# 03_ICs.net
KiCad netlist of a schematic drawn in Altium Designer
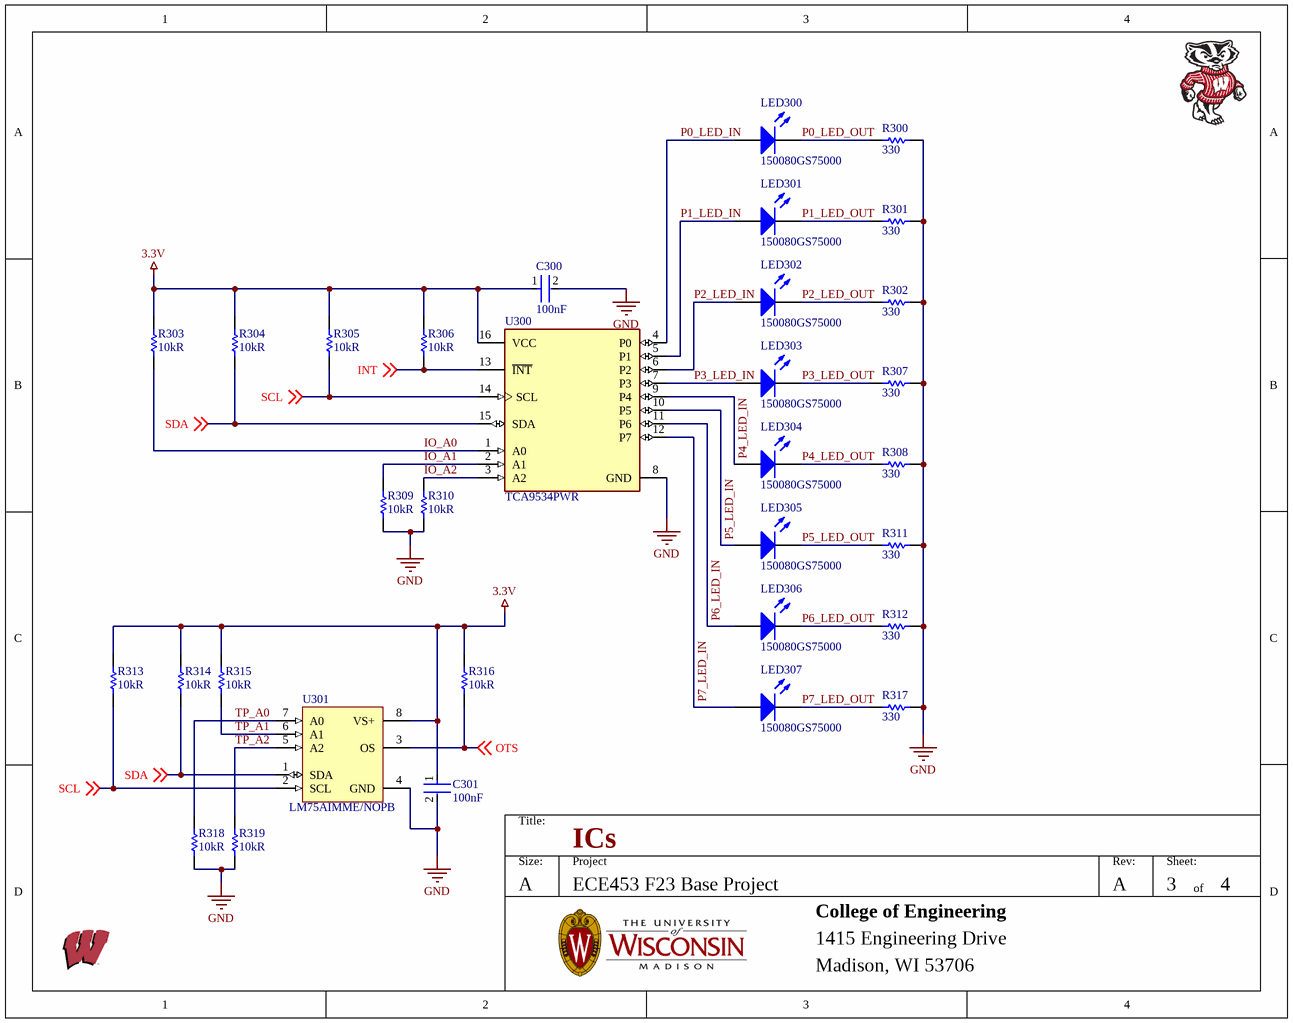
[diagram p0: 03_ICs.SchDoc]

(export (version "E")
  (design (tool "Eeschema 10.0.6"))
  (components
    (comp (ref "C300")
      (value "100nF")
      (footprint "FP-C0805C-DN-MFG")
      (description "CAP CER 0.1UF 50V X7R 0805")
      (fields
        (field (name "MANUFACTURER") "KEMET")
        (field (name "MANUFACTURER PART NUMBER") "C0805C104K5RACTU")
      )
      (libsource (lib "ECE453") (part "CMP-2007-00279-2"))
    )
    (comp (ref "C301")
      (value "100nF")
      (footprint "FP-C0805C-DN-MFG")
      (description "CAP CER 0.1UF 50V X7R 0805")
      (fields
        (field (name "MANUFACTURER") "KEMET")
        (field (name "MANUFACTURER PART NUMBER") "C0805C104K5RACTU")
      )
      (libsource (lib "ECE453") (part "CMP-2007-00279-2"))
    )
    (comp (ref "LED300")
      (value "150080GS75000")
      (footprint "0805_A")
      (description "SMD mono-color Chip LED, WL-SMCW, Green")
      (fields (field (name "MANUFACTURER") "Wuerth Elektronik"))
      (libsource (lib "ECE453") (part "CMP-1426-00007-1"))
    )
    (comp (ref "LED301")
      (value "150080GS75000")
      (footprint "0805_A")
      (description "SMD mono-color Chip LED, WL-SMCW, Green")
      (fields (field (name "MANUFACTURER") "Wuerth Elektronik"))
      (libsource (lib "ECE453") (part "CMP-1426-00007-1"))
    )
    (comp (ref "LED302")
      (value "150080GS75000")
      (footprint "0805_A")
      (description "SMD mono-color Chip LED, WL-SMCW, Green")
      (fields (field (name "MANUFACTURER") "Wuerth Elektronik"))
      (libsource (lib "ECE453") (part "CMP-1426-00007-1"))
    )
    (comp (ref "LED303")
      (value "150080GS75000")
      (footprint "0805_A")
      (description "SMD mono-color Chip LED, WL-SMCW, Green")
      (fields (field (name "MANUFACTURER") "Wuerth Elektronik"))
      (libsource (lib "ECE453") (part "CMP-1426-00007-1"))
    )
    (comp (ref "LED304")
      (value "150080GS75000")
      (footprint "0805_A")
      (description "SMD mono-color Chip LED, WL-SMCW, Green")
      (fields (field (name "MANUFACTURER") "Wuerth Elektronik"))
      (libsource (lib "ECE453") (part "CMP-1426-00007-1"))
    )
    (comp (ref "LED305")
      (value "150080GS75000")
      (footprint "0805_A")
      (description "SMD mono-color Chip LED, WL-SMCW, Green")
      (fields (field (name "MANUFACTURER") "Wuerth Elektronik"))
      (libsource (lib "ECE453") (part "CMP-1426-00007-1"))
    )
    (comp (ref "LED306")
      (value "150080GS75000")
      (footprint "0805_A")
      (description "SMD mono-color Chip LED, WL-SMCW, Green")
      (fields (field (name "MANUFACTURER") "Wuerth Elektronik"))
      (libsource (lib "ECE453") (part "CMP-1426-00007-1"))
    )
    (comp (ref "LED307")
      (value "150080GS75000")
      (footprint "0805_A")
      (description "SMD mono-color Chip LED, WL-SMCW, Green")
      (fields (field (name "MANUFACTURER") "Wuerth Elektronik"))
      (libsource (lib "ECE453") (part "CMP-1426-00007-1"))
    )
    (comp (ref "R300")
      (value "RC0805FR-07330RL")
      (footprint "RESC2013X60X35LL10T20")
      (description "Chip Resistor, 330 Ohm, +/- 1%, 125 mW, -55 to 155 degC, 0805 (2012 Metric), RoHS, Tape and Reel")
      (fields
        (field (name "MANUFACTURER") "Yageo")
        (field (name "TOLERANCE") "1%")
        (field (name "RESISTANCE") "330")
      )
      (libsource (lib "ECE453") (part "CMP-2000-06960-1"))
    )
    (comp (ref "R301")
      (value "RC0805FR-07330RL")
      (footprint "RESC2013X60X35LL10T20")
      (description "Chip Resistor, 330 Ohm, +/- 1%, 125 mW, -55 to 155 degC, 0805 (2012 Metric), RoHS, Tape and Reel")
      (fields
        (field (name "MANUFACTURER") "Yageo")
        (field (name "TOLERANCE") "1%")
        (field (name "RESISTANCE") "330")
      )
      (libsource (lib "ECE453") (part "CMP-2000-06960-1"))
    )
    (comp (ref "R302")
      (value "RC0805FR-07330RL")
      (footprint "RESC2013X60X35LL10T20")
      (description "Chip Resistor, 330 Ohm, +/- 1%, 125 mW, -55 to 155 degC, 0805 (2012 Metric), RoHS, Tape and Reel")
      (fields
        (field (name "MANUFACTURER") "Yageo")
        (field (name "TOLERANCE") "1%")
        (field (name "RESISTANCE") "330")
      )
      (libsource (lib "ECE453") (part "CMP-2000-06960-1"))
    )
    (comp (ref "R303")
      (value "RC0805FR-0710KL")
      (footprint "RESC2013X60X35NL10T20")
      (description "Chip Resistor, 10 KOhm, +/- 1%, 0.125 W, -55 to 155 degC, 0805 (2012 Metric), RoHS, Tape and Reel")
      (fields
        (field (name "MANUFACTURER") "Yageo")
        (field (name "RESISTANCE") "10kR")
        (field (name "TOLERANCE") "1%")
      )
      (libsource (lib "ECE453") (part "CMP-1659-00013-4"))
    )
    (comp (ref "R304")
      (value "RC0805FR-0710KL")
      (footprint "RESC2013X60X35NL10T20")
      (description "Chip Resistor, 10 KOhm, +/- 1%, 0.125 W, -55 to 155 degC, 0805 (2012 Metric), RoHS, Tape and Reel")
      (fields
        (field (name "MANUFACTURER") "Yageo")
        (field (name "RESISTANCE") "10kR")
        (field (name "TOLERANCE") "1%")
      )
      (libsource (lib "ECE453") (part "CMP-1659-00013-4"))
    )
    (comp (ref "R305")
      (value "RC0805FR-0710KL")
      (footprint "RESC2013X60X35NL10T20")
      (description "Chip Resistor, 10 KOhm, +/- 1%, 0.125 W, -55 to 155 degC, 0805 (2012 Metric), RoHS, Tape and Reel")
      (fields
        (field (name "MANUFACTURER") "Yageo")
        (field (name "RESISTANCE") "10kR")
        (field (name "TOLERANCE") "1%")
      )
      (libsource (lib "ECE453") (part "CMP-1659-00013-4"))
    )
    (comp (ref "R306")
      (value "RC0805FR-0710KL")
      (footprint "RESC2013X60X35NL10T20")
      (description "Chip Resistor, 10 KOhm, +/- 1%, 0.125 W, -55 to 155 degC, 0805 (2012 Metric), RoHS, Tape and Reel")
      (fields
        (field (name "MANUFACTURER") "Yageo")
        (field (name "RESISTANCE") "10kR")
        (field (name "TOLERANCE") "1%")
      )
      (libsource (lib "ECE453") (part "CMP-1659-00013-4"))
    )
    (comp (ref "R307")
      (value "RC0805FR-07330RL")
      (footprint "RESC2013X60X35LL10T20")
      (description "Chip Resistor, 330 Ohm, +/- 1%, 125 mW, -55 to 155 degC, 0805 (2012 Metric), RoHS, Tape and Reel")
      (fields
        (field (name "MANUFACTURER") "Yageo")
        (field (name "TOLERANCE") "1%")
        (field (name "RESISTANCE") "330")
      )
      (libsource (lib "ECE453") (part "CMP-2000-06960-1"))
    )
    (comp (ref "R308")
      (value "RC0805FR-07330RL")
      (footprint "RESC2013X60X35LL10T20")
      (description "Chip Resistor, 330 Ohm, +/- 1%, 125 mW, -55 to 155 degC, 0805 (2012 Metric), RoHS, Tape and Reel")
      (fields
        (field (name "MANUFACTURER") "Yageo")
        (field (name "TOLERANCE") "1%")
        (field (name "RESISTANCE") "330")
      )
      (libsource (lib "ECE453") (part "CMP-2000-06960-1"))
    )
    (comp (ref "R309")
      (value "RC0805FR-0710KL")
      (footprint "RESC2013X60X35NL10T20")
      (description "Chip Resistor, 10 KOhm, +/- 1%, 0.125 W, -55 to 155 degC, 0805 (2012 Metric), RoHS, Tape and Reel")
      (fields
        (field (name "MANUFACTURER") "Yageo")
        (field (name "RESISTANCE") "10kR")
        (field (name "TOLERANCE") "1%")
      )
      (libsource (lib "ECE453") (part "CMP-1659-00013-4"))
    )
    (comp (ref "R310")
      (value "RC0805FR-0710KL")
      (footprint "RESC2013X60X35NL10T20")
      (description "Chip Resistor, 10 KOhm, +/- 1%, 0.125 W, -55 to 155 degC, 0805 (2012 Metric), RoHS, Tape and Reel")
      (fields
        (field (name "MANUFACTURER") "Yageo")
        (field (name "RESISTANCE") "10kR")
        (field (name "TOLERANCE") "1%")
      )
      (libsource (lib "ECE453") (part "CMP-1659-00013-4"))
    )
    (comp (ref "R311")
      (value "RC0805FR-07330RL")
      (footprint "RESC2013X60X35LL10T20")
      (description "Chip Resistor, 330 Ohm, +/- 1%, 125 mW, -55 to 155 degC, 0805 (2012 Metric), RoHS, Tape and Reel")
      (fields
        (field (name "MANUFACTURER") "Yageo")
        (field (name "TOLERANCE") "1%")
        (field (name "RESISTANCE") "330")
      )
      (libsource (lib "ECE453") (part "CMP-2000-06960-1"))
    )
    (comp (ref "R312")
      (value "RC0805FR-07330RL")
      (footprint "RESC2013X60X35LL10T20")
      (description "Chip Resistor, 330 Ohm, +/- 1%, 125 mW, -55 to 155 degC, 0805 (2012 Metric), RoHS, Tape and Reel")
      (fields
        (field (name "MANUFACTURER") "Yageo")
        (field (name "TOLERANCE") "1%")
        (field (name "RESISTANCE") "330")
      )
      (libsource (lib "ECE453") (part "CMP-2000-06960-1"))
    )
    (comp (ref "R313")
      (value "RC0805FR-0710KL")
      (footprint "RESC2013X60X35NL10T20")
      (description "Chip Resistor, 10 KOhm, +/- 1%, 0.125 W, -55 to 155 degC, 0805 (2012 Metric), RoHS, Tape and Reel")
      (fields
        (field (name "MANUFACTURER") "Yageo")
        (field (name "RESISTANCE") "10kR")
        (field (name "TOLERANCE") "1%")
      )
      (libsource (lib "ECE453") (part "CMP-1659-00013-4"))
    )
    (comp (ref "R314")
      (value "RC0805FR-0710KL")
      (footprint "RESC2013X60X35NL10T20")
      (description "Chip Resistor, 10 KOhm, +/- 1%, 0.125 W, -55 to 155 degC, 0805 (2012 Metric), RoHS, Tape and Reel")
      (fields
        (field (name "MANUFACTURER") "Yageo")
        (field (name "RESISTANCE") "10kR")
        (field (name "TOLERANCE") "1%")
      )
      (libsource (lib "ECE453") (part "CMP-1659-00013-4"))
    )
    (comp (ref "R315")
      (value "RC0805FR-0710KL")
      (footprint "RESC2013X60X35NL10T20")
      (description "Chip Resistor, 10 KOhm, +/- 1%, 0.125 W, -55 to 155 degC, 0805 (2012 Metric), RoHS, Tape and Reel")
      (fields
        (field (name "MANUFACTURER") "Yageo")
        (field (name "RESISTANCE") "10kR")
        (field (name "TOLERANCE") "1%")
      )
      (libsource (lib "ECE453") (part "CMP-1659-00013-4"))
    )
    (comp (ref "R316")
      (value "RC0805FR-0710KL")
      (footprint "RESC2013X60X35NL10T20")
      (description "Chip Resistor, 10 KOhm, +/- 1%, 0.125 W, -55 to 155 degC, 0805 (2012 Metric), RoHS, Tape and Reel")
      (fields
        (field (name "MANUFACTURER") "Yageo")
        (field (name "RESISTANCE") "10kR")
        (field (name "TOLERANCE") "1%")
      )
      (libsource (lib "ECE453") (part "CMP-1659-00013-4"))
    )
    (comp (ref "R317")
      (value "RC0805FR-07330RL")
      (footprint "RESC2013X60X35LL10T20")
      (description "Chip Resistor, 330 Ohm, +/- 1%, 125 mW, -55 to 155 degC, 0805 (2012 Metric), RoHS, Tape and Reel")
      (fields
        (field (name "MANUFACTURER") "Yageo")
        (field (name "TOLERANCE") "1%")
        (field (name "RESISTANCE") "330")
      )
      (libsource (lib "ECE453") (part "CMP-2000-06960-1"))
    )
    (comp (ref "R318")
      (value "RC0805FR-0710KL")
      (footprint "RESC2013X60X35NL10T20")
      (description "Chip Resistor, 10 KOhm, +/- 1%, 0.125 W, -55 to 155 degC, 0805 (2012 Metric), RoHS, Tape and Reel")
      (fields
        (field (name "MANUFACTURER") "Yageo")
        (field (name "RESISTANCE") "10kR")
        (field (name "TOLERANCE") "1%")
      )
      (libsource (lib "ECE453") (part "CMP-1659-00013-4"))
    )
    (comp (ref "R319")
      (value "RC0805FR-0710KL")
      (footprint "RESC2013X60X35NL10T20")
      (description "Chip Resistor, 10 KOhm, +/- 1%, 0.125 W, -55 to 155 degC, 0805 (2012 Metric), RoHS, Tape and Reel")
      (fields
        (field (name "MANUFACTURER") "Yageo")
        (field (name "RESISTANCE") "10kR")
        (field (name "TOLERANCE") "1%")
      )
      (libsource (lib "ECE453") (part "CMP-1659-00013-4"))
    )
    (comp (ref "U300")
      (value "TCA9534PWR")
      (footprint "FP-PW0016A-IPC_C")
      (description "IC I/O EXPANDER I2C 8B 16TSSOP")
      (libsource (lib "ECE453") (part "CMP-04886-000003-2"))
    )
    (comp (ref "U301")
      (value "LM75AIMME/NOPB")
      (footprint "DGK0008A_L")
      (description "Digital Temperature Sensor and Thermal Watchdog with Two-Wire Interface, 8-pin Mini SOIC, Pb-Free")
      (fields (field (name "MANUFACTURER") "Texas Instruments"))
      (libsource (lib "Altium Content Vault") (part "SEN-TEMP-LM75-8"))
    )
  )
  (nets
    (net (code "1") (name "/IO_A0") (class "Default")
      (node (ref "R303") (pin "1") (pinfunction "1_1") (pintype "passive"))
      (node (ref "U300") (pin "1") (pinfunction "A0_1") (pintype "input"))
    )
    (net (code "2") (name "/IO_A1") (class "Default")
      (node (ref "R309") (pin "2") (pinfunction "2_2") (pintype "passive"))
      (node (ref "U300") (pin "2") (pinfunction "A1_2") (pintype "input"))
    )
    (net (code "3") (name "/IO_A2") (class "Default")
      (node (ref "R310") (pin "2") (pinfunction "2_2") (pintype "passive"))
      (node (ref "U300") (pin "3") (pinfunction "A2_3") (pintype "input"))
    )
    (net (code "4") (name "/P0_LED_IN") (class "Default")
      (node (ref "LED300") (pin "2") (pinfunction "A_2") (pintype "passive"))
      (node (ref "U300") (pin "4") (pinfunction "P0_4") (pintype "bidirectional"))
    )
    (net (code "5") (name "/P0_LED_OUT") (class "Default")
      (node (ref "LED300") (pin "1") (pinfunction "K_1") (pintype "passive"))
      (node (ref "R300") (pin "1") (pinfunction "1_1") (pintype "passive"))
    )
    (net (code "6") (name "/P1_LED_IN") (class "Default")
      (node (ref "LED301") (pin "2") (pinfunction "A_2") (pintype "passive"))
      (node (ref "U300") (pin "5") (pinfunction "P1_5") (pintype "bidirectional"))
    )
    (net (code "7") (name "/P1_LED_OUT") (class "Default")
      (node (ref "LED301") (pin "1") (pinfunction "K_1") (pintype "passive"))
      (node (ref "R301") (pin "1") (pinfunction "1_1") (pintype "passive"))
    )
    (net (code "8") (name "/P2_LED_IN") (class "Default")
      (node (ref "LED302") (pin "2") (pinfunction "A_2") (pintype "passive"))
      (node (ref "U300") (pin "6") (pinfunction "P2_6") (pintype "bidirectional"))
    )
    (net (code "9") (name "/P2_LED_OUT") (class "Default")
      (node (ref "LED302") (pin "1") (pinfunction "K_1") (pintype "passive"))
      (node (ref "R302") (pin "1") (pinfunction "1_1") (pintype "passive"))
    )
    (net (code "10") (name "/P3_LED_IN") (class "Default")
      (node (ref "LED303") (pin "2") (pinfunction "A_2") (pintype "passive"))
      (node (ref "U300") (pin "7") (pinfunction "P3_7") (pintype "bidirectional"))
    )
    (net (code "11") (name "/P3_LED_OUT") (class "Default")
      (node (ref "LED303") (pin "1") (pinfunction "K_1") (pintype "passive"))
      (node (ref "R307") (pin "1") (pinfunction "1_1") (pintype "passive"))
    )
    (net (code "12") (name "/P4_LED_IN") (class "Default")
      (node (ref "LED304") (pin "2") (pinfunction "A_2") (pintype "passive"))
      (node (ref "U300") (pin "9") (pinfunction "P4_9") (pintype "bidirectional"))
    )
    (net (code "13") (name "/P4_LED_OUT") (class "Default")
      (node (ref "LED304") (pin "1") (pinfunction "K_1") (pintype "passive"))
      (node (ref "R308") (pin "1") (pinfunction "1_1") (pintype "passive"))
    )
    (net (code "14") (name "/P5_LED_IN") (class "Default")
      (node (ref "LED305") (pin "2") (pinfunction "A_2") (pintype "passive"))
      (node (ref "U300") (pin "10") (pinfunction "P5_10") (pintype "bidirectional"))
    )
    (net (code "15") (name "/P5_LED_OUT") (class "Default")
      (node (ref "LED305") (pin "1") (pinfunction "K_1") (pintype "passive"))
      (node (ref "R311") (pin "1") (pinfunction "1_1") (pintype "passive"))
    )
    (net (code "16") (name "/P6_LED_IN") (class "Default")
      (node (ref "LED306") (pin "2") (pinfunction "A_2") (pintype "passive"))
      (node (ref "U300") (pin "11") (pinfunction "P6_11") (pintype "bidirectional"))
    )
    (net (code "17") (name "/P6_LED_OUT") (class "Default")
      (node (ref "LED306") (pin "1") (pinfunction "K_1") (pintype "passive"))
      (node (ref "R312") (pin "1") (pinfunction "1_1") (pintype "passive"))
    )
    (net (code "18") (name "/P7_LED_IN") (class "Default")
      (node (ref "LED307") (pin "2") (pinfunction "A_2") (pintype "passive"))
      (node (ref "U300") (pin "12") (pinfunction "P7_12") (pintype "bidirectional"))
    )
    (net (code "19") (name "/P7_LED_OUT") (class "Default")
      (node (ref "LED307") (pin "1") (pinfunction "K_1") (pintype "passive"))
      (node (ref "R317") (pin "1") (pinfunction "1_1") (pintype "passive"))
    )
    (net (code "20") (name "/TP_A0") (class "Default")
      (node (ref "R318") (pin "2") (pinfunction "2_2") (pintype "passive"))
      (node (ref "U301") (pin "7") (pinfunction "A0_7") (pintype "input"))
    )
    (net (code "21") (name "/TP_A1") (class "Default")
      (node (ref "R315") (pin "1") (pinfunction "1_1") (pintype "passive"))
      (node (ref "U301") (pin "6") (pinfunction "A1_6") (pintype "input"))
    )
    (net (code "22") (name "/TP_A2") (class "Default")
      (node (ref "R319") (pin "2") (pinfunction "2_2") (pintype "passive"))
      (node (ref "U301") (pin "5") (pinfunction "A2_5") (pintype "input"))
    )
    (net (code "23") (name "3.3V") (class "Default")
      (node (ref "C300") (pin "1") (pinfunction "1_1") (pintype "passive"))
      (node (ref "C301") (pin "1") (pinfunction "1_1") (pintype "passive"))
      (node (ref "R303") (pin "2") (pinfunction "2_2") (pintype "passive"))
      (node (ref "R304") (pin "2") (pinfunction "2_2") (pintype "passive"))
      (node (ref "R305") (pin "2") (pinfunction "2_2") (pintype "passive"))
      (node (ref "R306") (pin "2") (pinfunction "2_2") (pintype "passive"))
      (node (ref "R313") (pin "2") (pinfunction "2_2") (pintype "passive"))
      (node (ref "R314") (pin "2") (pinfunction "2_2") (pintype "passive"))
      (node (ref "R315") (pin "2") (pinfunction "2_2") (pintype "passive"))
      (node (ref "R316") (pin "2") (pinfunction "2_2") (pintype "passive"))
      (node (ref "U300") (pin "16") (pinfunction "VCC_16") (pintype "power_in"))
      (node (ref "U301") (pin "8") (pinfunction "VS+_8") (pintype "power_in"))
    )
    (net (code "24") (name "GND") (class "Default")
      (node (ref "C300") (pin "2") (pinfunction "2_2") (pintype "passive"))
      (node (ref "C301") (pin "2") (pinfunction "2_2") (pintype "passive"))
      (node (ref "R300") (pin "2") (pinfunction "2_2") (pintype "passive"))
      (node (ref "R301") (pin "2") (pinfunction "2_2") (pintype "passive"))
      (node (ref "R302") (pin "2") (pinfunction "2_2") (pintype "passive"))
      (node (ref "R307") (pin "2") (pinfunction "2_2") (pintype "passive"))
      (node (ref "R308") (pin "2") (pinfunction "2_2") (pintype "passive"))
      (node (ref "R309") (pin "1") (pinfunction "1_1") (pintype "passive"))
      (node (ref "R310") (pin "1") (pinfunction "1_1") (pintype "passive"))
      (node (ref "R311") (pin "2") (pinfunction "2_2") (pintype "passive"))
      (node (ref "R312") (pin "2") (pinfunction "2_2") (pintype "passive"))
      (node (ref "R317") (pin "2") (pinfunction "2_2") (pintype "passive"))
      (node (ref "R318") (pin "1") (pinfunction "1_1") (pintype "passive"))
      (node (ref "R319") (pin "1") (pinfunction "1_1") (pintype "passive"))
      (node (ref "U300") (pin "8") (pinfunction "GND_8") (pintype "power_in"))
      (node (ref "U301") (pin "4") (pinfunction "GND_4") (pintype "power_in"))
    )
    (net (code "25") (name "INT") (class "Default")
      (node (ref "R306") (pin "1") (pinfunction "1_1") (pintype "passive"))
      (node (ref "U300") (pin "13") (pinfunction "~{INT}_13") (pintype "open_collector"))
    )
    (net (code "26") (name "OTS") (class "Default")
      (node (ref "R316") (pin "1") (pinfunction "1_1") (pintype "passive"))
      (node (ref "U301") (pin "3") (pinfunction "OS_3") (pintype "open_collector"))
    )
    (net (code "27") (name "SCL") (class "Default")
      (node (ref "R305") (pin "1") (pinfunction "1_1") (pintype "passive"))
      (node (ref "R313") (pin "1") (pinfunction "1_1") (pintype "passive"))
      (node (ref "U300") (pin "14") (pinfunction "SCL_14") (pintype "input"))
      (node (ref "U301") (pin "2") (pinfunction "SCL_2") (pintype "input"))
    )
    (net (code "28") (name "SDA") (class "Default")
      (node (ref "R304") (pin "1") (pinfunction "1_1") (pintype "passive"))
      (node (ref "R314") (pin "1") (pinfunction "1_1") (pintype "passive"))
      (node (ref "U300") (pin "15") (pinfunction "SDA_15") (pintype "bidirectional"))
      (node (ref "U301") (pin "1") (pinfunction "SDA_1") (pintype "bidirectional"))
    )
  )
)
